# usbjtag.net
KiCad netlist of a schematic drawn in EAGLE
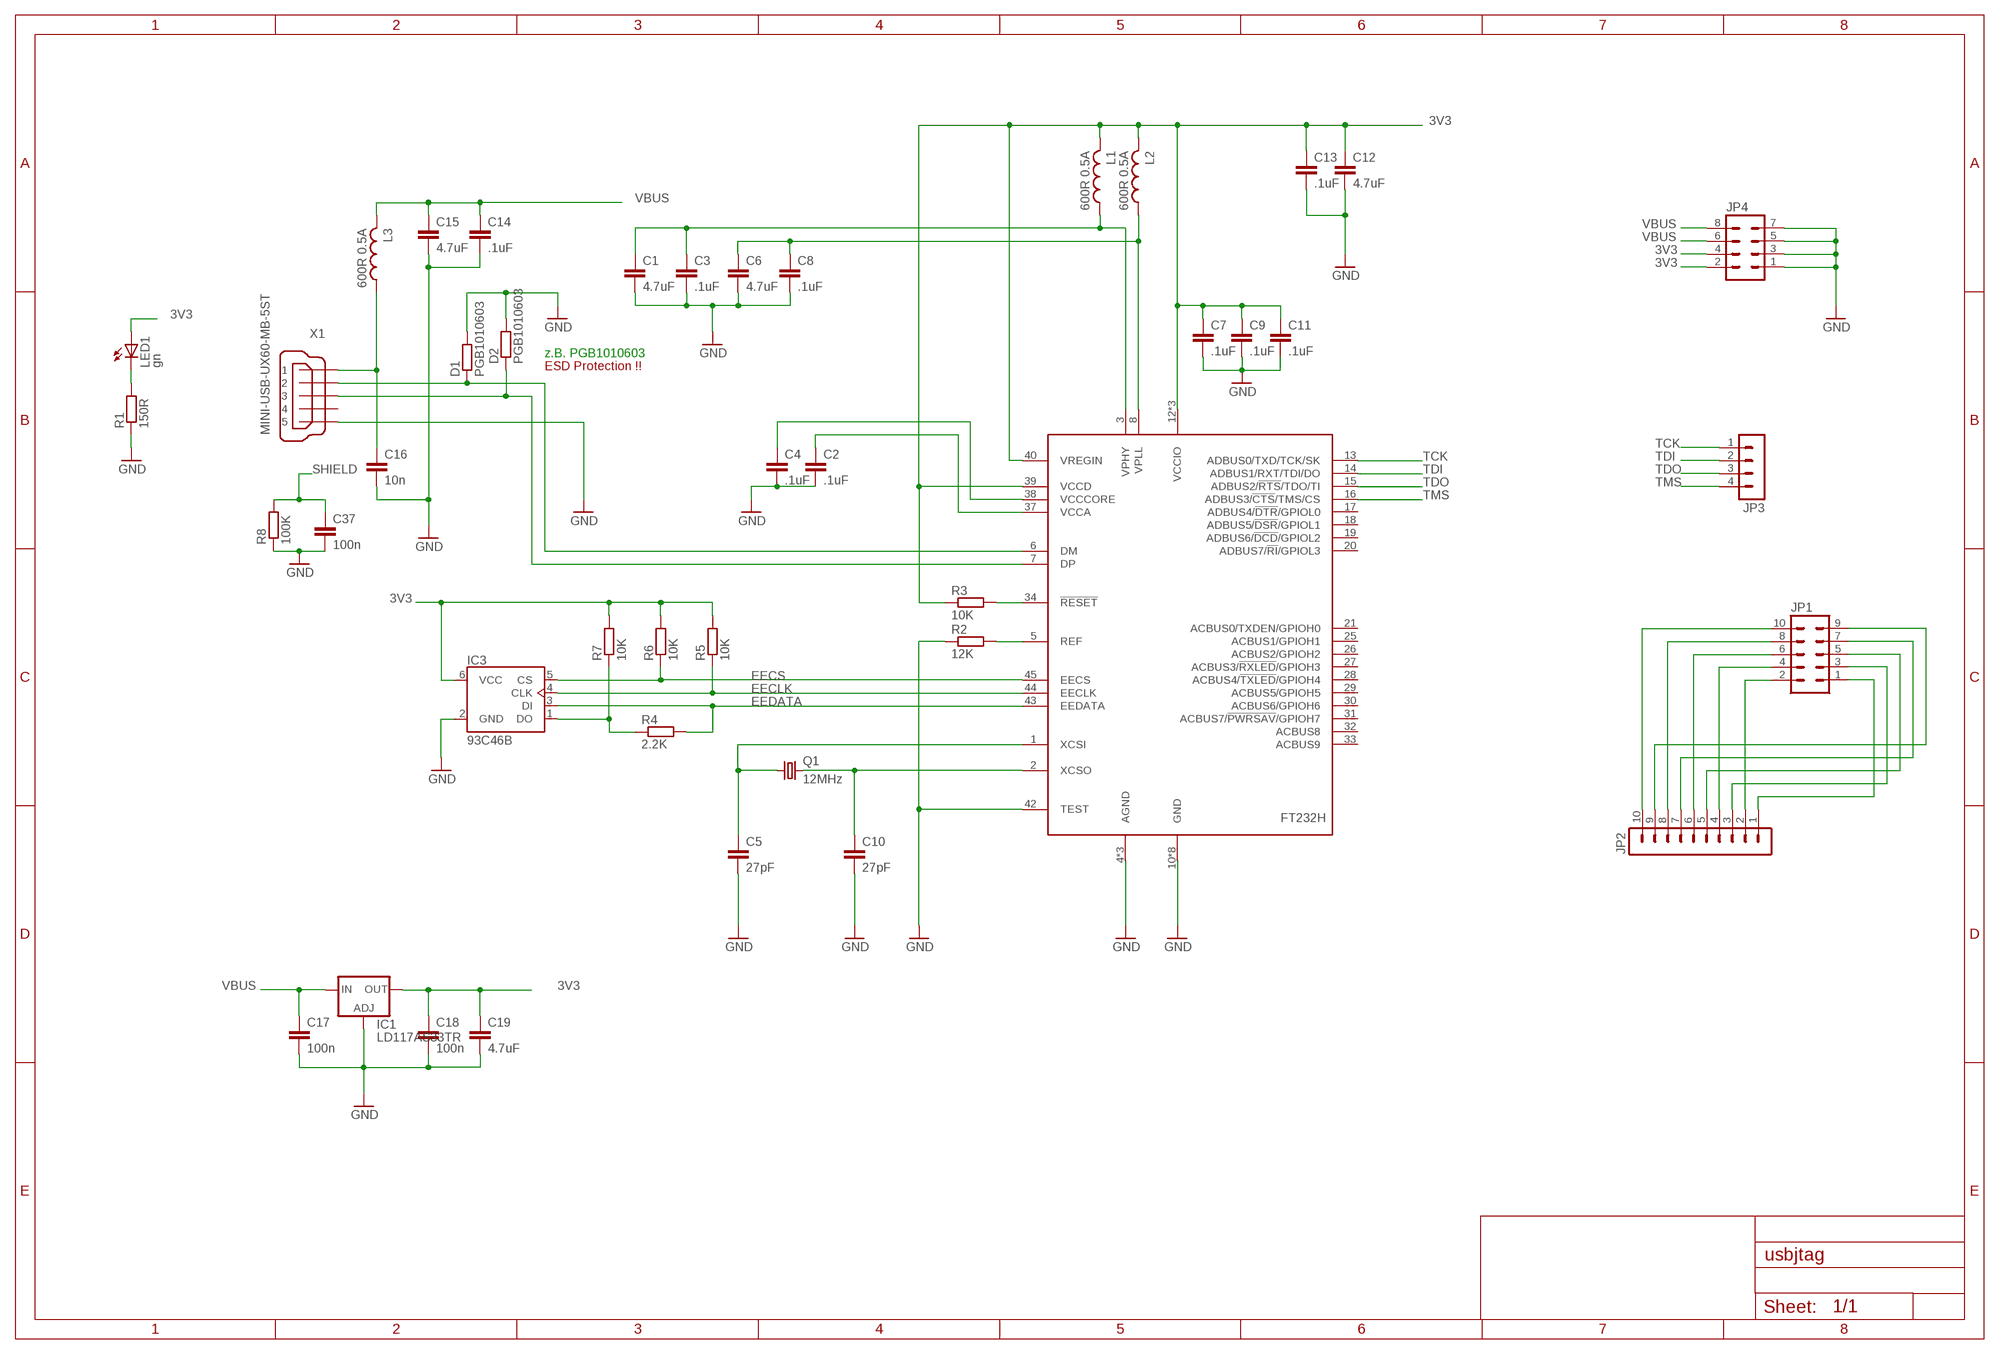
[diagram p0: schematic, sheet 1]

(export (version "E")
  (design (tool "Eeschema 10.0.6"))
  (components
    (comp (ref "C1")
      (value "4.7uF")
      (footprint "eagle-import:C0805")
      (libsource (lib "eagle-import") (part "C-EUC0805"))
    )
    (comp (ref "C2")
      (value ".1uF")
      (footprint "eagle-import:C0805")
      (libsource (lib "eagle-import") (part "C-EUC0805"))
    )
    (comp (ref "C3")
      (value ".1uF")
      (footprint "eagle-import:C0805")
      (libsource (lib "eagle-import") (part "C-EUC0805"))
    )
    (comp (ref "C4")
      (value ".1uF")
      (footprint "eagle-import:C0805")
      (libsource (lib "eagle-import") (part "C-EUC0805"))
    )
    (comp (ref "C5")
      (value "27pF")
      (footprint "eagle-import:C0805")
      (libsource (lib "eagle-import") (part "C-EUC0805"))
    )
    (comp (ref "C6")
      (value "4.7uF")
      (footprint "eagle-import:C0805")
      (libsource (lib "eagle-import") (part "C-EUC0805"))
    )
    (comp (ref "C7")
      (value ".1uF")
      (footprint "eagle-import:C0805")
      (libsource (lib "eagle-import") (part "C-EUC0805"))
    )
    (comp (ref "C8")
      (value ".1uF")
      (footprint "eagle-import:C0805")
      (libsource (lib "eagle-import") (part "C-EUC0805"))
    )
    (comp (ref "C9")
      (value ".1uF")
      (footprint "eagle-import:C0805")
      (libsource (lib "eagle-import") (part "C-EUC0805"))
    )
    (comp (ref "C10")
      (value "27pF")
      (footprint "eagle-import:C0805")
      (libsource (lib "eagle-import") (part "C-EUC0805"))
    )
    (comp (ref "C11")
      (value ".1uF")
      (footprint "eagle-import:C0805")
      (libsource (lib "eagle-import") (part "C-EUC0805"))
    )
    (comp (ref "C12")
      (value "4.7uF")
      (footprint "eagle-import:C0805")
      (libsource (lib "eagle-import") (part "C-EUC0805"))
    )
    (comp (ref "C13")
      (value ".1uF")
      (footprint "eagle-import:C0805")
      (libsource (lib "eagle-import") (part "C-EUC0805"))
    )
    (comp (ref "C14")
      (value ".1uF")
      (footprint "eagle-import:C0805")
      (libsource (lib "eagle-import") (part "C-EUC0805"))
    )
    (comp (ref "C15")
      (value "4.7uF")
      (footprint "eagle-import:C0805")
      (libsource (lib "eagle-import") (part "C-EUC0805"))
    )
    (comp (ref "C16")
      (value "10n")
      (footprint "eagle-import:C0805")
      (libsource (lib "eagle-import") (part "C-EUC0805"))
    )
    (comp (ref "C17")
      (value "100n")
      (footprint "eagle-import:C0805")
      (libsource (lib "eagle-import") (part "C-EUC0805"))
    )
    (comp (ref "C18")
      (value "100n")
      (footprint "eagle-import:C0805")
      (libsource (lib "eagle-import") (part "C-EUC0805"))
    )
    (comp (ref "C19")
      (value "4.7uF")
      (footprint "eagle-import:C0805")
      (libsource (lib "eagle-import") (part "C-EUC0805"))
    )
    (comp (ref "C37")
      (value "100n")
      (footprint "eagle-import:C0805")
      (libsource (lib "eagle-import") (part "C-EUC0805"))
    )
    (comp (ref "D1")
      (value "PGB1010603")
      (footprint "eagle-import:R0603")
      (libsource (lib "eagle-import") (part "R-EU_R0603"))
    )
    (comp (ref "D2")
      (value "PGB1010603")
      (footprint "eagle-import:R0603")
      (libsource (lib "eagle-import") (part "R-EU_R0603"))
    )
    (comp (ref "IC1")
      (value "LD117AS33TR")
      (footprint "eagle-import:SOT223")
      (libsource (lib "eagle-import") (part "LD117A?S33TR"))
    )
    (comp (ref "IC2")
      (value "FT232H")
      (footprint "eagle-import:LQFP48")
      (libsource (lib "eagle-import") (part "FT232H"))
    )
    (comp (ref "IC3")
      (value "93C46B")
      (footprint "eagle-import:SOT23-6")
      (libsource (lib "eagle-import") (part "DIGITAL-EEPROM-MICROWIRE-6P_SOT23"))
    )
    (comp (ref "JP1")
      (value "MA05-2")
      (footprint "eagle-import:MA05-2")
      (libsource (lib "eagle-import") (part "MA05-2"))
    )
    (comp (ref "JP2")
      (value "MA10-1")
      (footprint "eagle-import:MA10-1")
      (libsource (lib "eagle-import") (part "MA10-1"))
    )
    (comp (ref "JP3")
      (value "MA04-1")
      (footprint "eagle-import:MA04-1")
      (libsource (lib "eagle-import") (part "MA04-1"))
    )
    (comp (ref "JP4")
      (value "MA04-2")
      (footprint "eagle-import:MA04-2")
      (libsource (lib "eagle-import") (part "MA04-2"))
    )
    (comp (ref "L1")
      (value "600R 0.5A")
      (footprint "eagle-import:L4532M")
      (libsource (lib "eagle-import") (part "L-USL4532C"))
    )
    (comp (ref "L2")
      (value "600R 0.5A")
      (footprint "eagle-import:L4532M")
      (libsource (lib "eagle-import") (part "L-USL4532C"))
    )
    (comp (ref "L3")
      (value "600R 0.5A")
      (footprint "eagle-import:L4532M")
      (libsource (lib "eagle-import") (part "L-USL4532C"))
    )
    (comp (ref "LED1")
      (value "gn")
      (footprint "eagle-import:CHIPLED_0805")
      (libsource (lib "eagle-import") (part "LEDCHIPLED_0805"))
    )
    (comp (ref "Q1")
      (value "12MHz")
      (footprint "eagle-import:CRYSTAL3.2X2.5MM")
      (libsource (lib "eagle-import") (part "CRYSTAL3.2X2.5"))
    )
    (comp (ref "R1")
      (value "150R")
      (footprint "eagle-import:R0805")
      (libsource (lib "eagle-import") (part "R-EU_R0805"))
    )
    (comp (ref "R2")
      (value "12K")
      (footprint "eagle-import:R0805")
      (libsource (lib "eagle-import") (part "R-EU_R0805"))
    )
    (comp (ref "R3")
      (value "10K")
      (footprint "eagle-import:R0805")
      (libsource (lib "eagle-import") (part "R-EU_R0805"))
    )
    (comp (ref "R4")
      (value "2.2K")
      (footprint "eagle-import:R0805")
      (libsource (lib "eagle-import") (part "R-EU_R0805"))
    )
    (comp (ref "R5")
      (value "10K")
      (footprint "eagle-import:R0805")
      (libsource (lib "eagle-import") (part "R-EU_R0805"))
    )
    (comp (ref "R6")
      (value "10K")
      (footprint "eagle-import:R0805")
      (libsource (lib "eagle-import") (part "R-EU_R0805"))
    )
    (comp (ref "R7")
      (value "10K")
      (footprint "eagle-import:R0805")
      (libsource (lib "eagle-import") (part "R-EU_R0805"))
    )
    (comp (ref "R8")
      (value "100K")
      (footprint "eagle-import:R0805")
      (libsource (lib "eagle-import") (part "R-EU_R0805"))
    )
    (comp (ref "X1")
      (value "MINI-USB-UX60-MB-5ST")
      (footprint "eagle-import:UX60-MB-5ST")
      (libsource (lib "eagle-import") (part "MINI-USB-UX60-MB-5ST"))
    )
  )
  (nets
    (net (code "1") (name "/3V3") (class "Default")
      (node (ref "C11") (pin "1") (pinfunction "1_1") (pintype "passive"))
      (node (ref "C12") (pin "1") (pinfunction "1_1") (pintype "passive"))
      (node (ref "C13") (pin "1") (pinfunction "1_1") (pintype "passive"))
      (node (ref "C18") (pin "1") (pinfunction "1_1") (pintype "passive"))
      (node (ref "C19") (pin "1") (pinfunction "1_1") (pintype "passive"))
      (node (ref "C7") (pin "1") (pinfunction "1_1") (pintype "passive"))
      (node (ref "C9") (pin "1") (pinfunction "1_1") (pintype "passive"))
      (node (ref "IC1") (pin "4") (pinfunction "OUT_4") (pintype "passive"))
      (node (ref "IC2") (pin "12") (pinfunction "VCCIO_12") (pintype "power_in"))
      (node (ref "IC2") (pin "24") (pinfunction "VCCIO_24") (pintype "power_in"))
      (node (ref "IC2") (pin "39") (pinfunction "VCCD_39") (pintype "power_in"))
      (node (ref "IC2") (pin "40") (pinfunction "VREGIN_40") (pintype "power_in"))
      (node (ref "IC2") (pin "46") (pinfunction "VCCIO_46") (pintype "power_in"))
      (node (ref "IC3") (pin "6") (pinfunction "VCC_6") (pintype "input"))
      (node (ref "JP4") (pin "2") (pinfunction "2_2") (pintype "passive"))
      (node (ref "JP4") (pin "4") (pinfunction "4_4") (pintype "passive"))
      (node (ref "L1") (pin "2") (pinfunction "2_2") (pintype "passive"))
      (node (ref "L2") (pin "2") (pinfunction "2_2") (pintype "passive"))
      (node (ref "LED1") (pin "A") (pinfunction "A_A") (pintype "passive"))
      (node (ref "R3") (pin "1") (pinfunction "1_1") (pintype "passive"))
      (node (ref "R5") (pin "2") (pinfunction "2_2") (pintype "passive"))
      (node (ref "R6") (pin "2") (pinfunction "2_2") (pintype "passive"))
      (node (ref "R7") (pin "2") (pinfunction "2_2") (pintype "passive"))
    )
    (net (code "2") (name "/EECLK") (class "Default")
      (node (ref "IC2") (pin "44") (pinfunction "EECLK_44") (pintype "bidirectional"))
      (node (ref "IC3") (pin "4") (pinfunction "CLK_4") (pintype "input"))
      (node (ref "R5") (pin "1") (pinfunction "1_1") (pintype "passive"))
    )
    (net (code "3") (name "/EECS") (class "Default")
      (node (ref "IC2") (pin "45") (pinfunction "EECS_45") (pintype "bidirectional"))
      (node (ref "IC3") (pin "5") (pinfunction "CS_5") (pintype "input"))
      (node (ref "R6") (pin "1") (pinfunction "1_1") (pintype "passive"))
    )
    (net (code "4") (name "/EEDATA") (class "Default")
      (node (ref "IC2") (pin "43") (pinfunction "EEDATA_43") (pintype "bidirectional"))
      (node (ref "IC3") (pin "3") (pinfunction "DI_3") (pintype "input"))
      (node (ref "R4") (pin "2") (pinfunction "2_2") (pintype "passive"))
    )
    (net (code "5") (name "/SHIELD") (class "Default")
      (node (ref "C37") (pin "1") (pinfunction "1_1") (pintype "passive"))
      (node (ref "R8") (pin "2") (pinfunction "2_2") (pintype "passive"))
    )
    (net (code "6") (name "/TCK") (class "Default")
      (node (ref "IC2") (pin "13") (pinfunction "ADBUS0/TXD/TCK/SK_13") (pintype "bidirectional"))
      (node (ref "JP3") (pin "1") (pinfunction "1_1") (pintype "passive"))
    )
    (net (code "7") (name "/TDI") (class "Default")
      (node (ref "IC2") (pin "14") (pinfunction "ADBUS1/RXT/TDI/DO_14") (pintype "bidirectional"))
      (node (ref "JP3") (pin "2") (pinfunction "2_2") (pintype "passive"))
    )
    (net (code "8") (name "/TDO") (class "Default")
      (node (ref "IC2") (pin "15") (pinfunction "ADBUS2/~{RTS}/TDO/TI_15") (pintype "bidirectional"))
      (node (ref "JP3") (pin "3") (pinfunction "3_3") (pintype "passive"))
    )
    (net (code "9") (name "/TMS") (class "Default")
      (node (ref "IC2") (pin "16") (pinfunction "ADBUS3/~{CTS}/TMS/CS_16") (pintype "bidirectional"))
      (node (ref "JP3") (pin "4") (pinfunction "4_4") (pintype "passive"))
    )
    (net (code "10") (name "/VBUS") (class "Default")
      (node (ref "C14") (pin "1") (pinfunction "1_1") (pintype "passive"))
      (node (ref "C15") (pin "1") (pinfunction "1_1") (pintype "passive"))
      (node (ref "C17") (pin "1") (pinfunction "1_1") (pintype "passive"))
      (node (ref "IC1") (pin "3") (pinfunction "IN_3") (pintype "input"))
      (node (ref "JP4") (pin "6") (pinfunction "6_6") (pintype "passive"))
      (node (ref "JP4") (pin "8") (pinfunction "8_8") (pintype "passive"))
      (node (ref "L3") (pin "2") (pinfunction "2_2") (pintype "passive"))
    )
    (net (code "11") (name "GND") (class "Default")
      (node (ref "C1") (pin "2") (pinfunction "2_2") (pintype "passive"))
      (node (ref "C10") (pin "2") (pinfunction "2_2") (pintype "passive"))
      (node (ref "C11") (pin "2") (pinfunction "2_2") (pintype "passive"))
      (node (ref "C12") (pin "2") (pinfunction "2_2") (pintype "passive"))
      (node (ref "C13") (pin "2") (pinfunction "2_2") (pintype "passive"))
      (node (ref "C14") (pin "2") (pinfunction "2_2") (pintype "passive"))
      (node (ref "C15") (pin "2") (pinfunction "2_2") (pintype "passive"))
      (node (ref "C16") (pin "2") (pinfunction "2_2") (pintype "passive"))
      (node (ref "C17") (pin "2") (pinfunction "2_2") (pintype "passive"))
      (node (ref "C18") (pin "2") (pinfunction "2_2") (pintype "passive"))
      (node (ref "C19") (pin "2") (pinfunction "2_2") (pintype "passive"))
      (node (ref "C2") (pin "2") (pinfunction "2_2") (pintype "passive"))
      (node (ref "C3") (pin "2") (pinfunction "2_2") (pintype "passive"))
      (node (ref "C37") (pin "2") (pinfunction "2_2") (pintype "passive"))
      (node (ref "C4") (pin "2") (pinfunction "2_2") (pintype "passive"))
      (node (ref "C5") (pin "2") (pinfunction "2_2") (pintype "passive"))
      (node (ref "C6") (pin "2") (pinfunction "2_2") (pintype "passive"))
      (node (ref "C7") (pin "2") (pinfunction "2_2") (pintype "passive"))
      (node (ref "C8") (pin "2") (pinfunction "2_2") (pintype "passive"))
      (node (ref "C9") (pin "2") (pinfunction "2_2") (pintype "passive"))
      (node (ref "D1") (pin "2") (pinfunction "2_2") (pintype "passive"))
      (node (ref "D2") (pin "2") (pinfunction "2_2") (pintype "passive"))
      (node (ref "IC1") (pin "1") (pinfunction "ADJ_1") (pintype "input"))
      (node (ref "IC2") (pin "10") (pinfunction "GND_10") (pintype "power_in"))
      (node (ref "IC2") (pin "11") (pinfunction "GND_11") (pintype "power_in"))
      (node (ref "IC2") (pin "22") (pinfunction "GND_22") (pintype "power_in"))
      (node (ref "IC2") (pin "23") (pinfunction "GND_23") (pintype "power_in"))
      (node (ref "IC2") (pin "35") (pinfunction "GND_35") (pintype "power_in"))
      (node (ref "IC2") (pin "36") (pinfunction "GND_36") (pintype "power_in"))
      (node (ref "IC2") (pin "4") (pinfunction "AGND_4") (pintype "power_in"))
      (node (ref "IC2") (pin "41") (pinfunction "AGND_41") (pintype "power_in"))
      (node (ref "IC2") (pin "42") (pinfunction "TEST_42") (pintype "bidirectional"))
      (node (ref "IC2") (pin "47") (pinfunction "GND_47") (pintype "power_in"))
      (node (ref "IC2") (pin "48") (pinfunction "GND_48") (pintype "power_in"))
      (node (ref "IC2") (pin "9") (pinfunction "AGND_9") (pintype "power_in"))
      (node (ref "IC3") (pin "2") (pinfunction "GND_2") (pintype "power_in"))
      (node (ref "JP4") (pin "1") (pinfunction "1_1") (pintype "passive"))
      (node (ref "JP4") (pin "3") (pinfunction "3_3") (pintype "passive"))
      (node (ref "JP4") (pin "5") (pinfunction "5_5") (pintype "passive"))
      (node (ref "JP4") (pin "7") (pinfunction "7_7") (pintype "passive"))
      (node (ref "R1") (pin "1") (pinfunction "1_1") (pintype "passive"))
      (node (ref "R2") (pin "1") (pinfunction "1_1") (pintype "passive"))
      (node (ref "R8") (pin "1") (pinfunction "1_1") (pintype "passive"))
      (node (ref "X1") (pin "5") (pinfunction "5_5") (pintype "input"))
    )
    (net (code "12") (name "Net-(C16-Pad1)") (class "Default")
      (node (ref "C16") (pin "1") (pinfunction "1_1") (pintype "passive"))
      (node (ref "L3") (pin "1") (pinfunction "1_1") (pintype "passive"))
      (node (ref "X1") (pin "1") (pinfunction "1_1") (pintype "input"))
    )
    (net (code "13") (name "Net-(IC2-DM)") (class "Default")
      (node (ref "D1") (pin "1") (pinfunction "1_1") (pintype "passive"))
      (node (ref "IC2") (pin "6") (pinfunction "DM_6") (pintype "bidirectional"))
      (node (ref "X1") (pin "2") (pinfunction "2_2") (pintype "input"))
    )
    (net (code "14") (name "Net-(IC2-DP)") (class "Default")
      (node (ref "D2") (pin "1") (pinfunction "1_1") (pintype "passive"))
      (node (ref "IC2") (pin "7") (pinfunction "DP_7") (pintype "bidirectional"))
      (node (ref "X1") (pin "3") (pinfunction "3_3") (pintype "input"))
    )
    (net (code "15") (name "Net-(IC2-REF)") (class "Default")
      (node (ref "IC2") (pin "5") (pinfunction "REF_5") (pintype "bidirectional"))
      (node (ref "R2") (pin "2") (pinfunction "2_2") (pintype "passive"))
    )
    (net (code "16") (name "Net-(IC2-VCCA)") (class "Default")
      (node (ref "C2") (pin "1") (pinfunction "1_1") (pintype "passive"))
      (node (ref "IC2") (pin "37") (pinfunction "VCCA_37") (pintype "power_in"))
    )
    (net (code "17") (name "Net-(IC2-VCCCORE)") (class "Default")
      (node (ref "C4") (pin "1") (pinfunction "1_1") (pintype "passive"))
      (node (ref "IC2") (pin "38") (pinfunction "VCCCORE_38") (pintype "power_in"))
    )
    (net (code "18") (name "Net-(IC2-VPHY)") (class "Default")
      (node (ref "C1") (pin "1") (pinfunction "1_1") (pintype "passive"))
      (node (ref "C3") (pin "1") (pinfunction "1_1") (pintype "passive"))
      (node (ref "IC2") (pin "3") (pinfunction "VPHY_3") (pintype "power_in"))
      (node (ref "L1") (pin "1") (pinfunction "1_1") (pintype "passive"))
    )
    (net (code "19") (name "Net-(IC2-VPLL)") (class "Default")
      (node (ref "C6") (pin "1") (pinfunction "1_1") (pintype "passive"))
      (node (ref "C8") (pin "1") (pinfunction "1_1") (pintype "passive"))
      (node (ref "IC2") (pin "8") (pinfunction "VPLL_8") (pintype "power_in"))
      (node (ref "L2") (pin "1") (pinfunction "1_1") (pintype "passive"))
    )
    (net (code "20") (name "Net-(IC2-XCSI)") (class "Default")
      (node (ref "C5") (pin "1") (pinfunction "1_1") (pintype "passive"))
      (node (ref "IC2") (pin "1") (pinfunction "XCSI_1") (pintype "bidirectional"))
      (node (ref "Q1") (pin "1") (pinfunction "1_1") (pintype "passive"))
    )
    (net (code "21") (name "Net-(IC2-XCSO)") (class "Default")
      (node (ref "C10") (pin "1") (pinfunction "1_1") (pintype "passive"))
      (node (ref "IC2") (pin "2") (pinfunction "XCSO_2") (pintype "bidirectional"))
      (node (ref "Q1") (pin "3") (pinfunction "2_3") (pintype "passive"))
    )
    (net (code "22") (name "Net-(IC2-~{RESET})") (class "Default")
      (node (ref "IC2") (pin "34") (pinfunction "~{RESET}_34") (pintype "input"))
      (node (ref "R3") (pin "2") (pinfunction "2_2") (pintype "passive"))
    )
    (net (code "23") (name "Net-(IC3-DO)") (class "Default")
      (node (ref "IC3") (pin "1") (pinfunction "DO_1") (pintype "output"))
      (node (ref "R4") (pin "1") (pinfunction "1_1") (pintype "passive"))
      (node (ref "R7") (pin "1") (pinfunction "1_1") (pintype "passive"))
    )
    (net (code "24") (name "Net-(JP1-Pad1)") (class "Default")
      (node (ref "JP1") (pin "1") (pinfunction "1_1") (pintype "passive"))
      (node (ref "JP2") (pin "1") (pinfunction "1_1") (pintype "passive"))
    )
    (net (code "25") (name "Net-(JP1-Pad2)") (class "Default")
      (node (ref "JP1") (pin "2") (pinfunction "2_2") (pintype "passive"))
      (node (ref "JP2") (pin "2") (pinfunction "2_2") (pintype "passive"))
    )
    (net (code "26") (name "Net-(JP1-Pad3)") (class "Default")
      (node (ref "JP1") (pin "3") (pinfunction "3_3") (pintype "passive"))
      (node (ref "JP2") (pin "3") (pinfunction "3_3") (pintype "passive"))
    )
    (net (code "27") (name "Net-(JP1-Pad4)") (class "Default")
      (node (ref "JP1") (pin "4") (pinfunction "4_4") (pintype "passive"))
      (node (ref "JP2") (pin "4") (pinfunction "4_4") (pintype "passive"))
    )
    (net (code "28") (name "Net-(JP1-Pad5)") (class "Default")
      (node (ref "JP1") (pin "5") (pinfunction "5_5") (pintype "passive"))
      (node (ref "JP2") (pin "5") (pinfunction "5_5") (pintype "passive"))
    )
    (net (code "29") (name "Net-(JP1-Pad6)") (class "Default")
      (node (ref "JP1") (pin "6") (pinfunction "6_6") (pintype "passive"))
      (node (ref "JP2") (pin "6") (pinfunction "6_6") (pintype "passive"))
    )
    (net (code "30") (name "Net-(JP1-Pad7)") (class "Default")
      (node (ref "JP1") (pin "7") (pinfunction "7_7") (pintype "passive"))
      (node (ref "JP2") (pin "7") (pinfunction "7_7") (pintype "passive"))
    )
    (net (code "31") (name "Net-(JP1-Pad8)") (class "Default")
      (node (ref "JP1") (pin "8") (pinfunction "8_8") (pintype "passive"))
      (node (ref "JP2") (pin "8") (pinfunction "8_8") (pintype "passive"))
    )
    (net (code "32") (name "Net-(JP1-Pad9)") (class "Default")
      (node (ref "JP1") (pin "9") (pinfunction "9_9") (pintype "passive"))
      (node (ref "JP2") (pin "9") (pinfunction "9_9") (pintype "passive"))
    )
    (net (code "33") (name "Net-(JP1-Pad10)") (class "Default")
      (node (ref "JP1") (pin "10") (pinfunction "10_10") (pintype "passive"))
      (node (ref "JP2") (pin "10") (pinfunction "10_10") (pintype "passive"))
    )
    (net (code "34") (name "Net-(LED1-PadC)") (class "Default")
      (node (ref "LED1") (pin "C") (pinfunction "C_C") (pintype "passive"))
      (node (ref "R1") (pin "2") (pinfunction "2_2") (pintype "passive"))
    )
    (net (code "35") (name "unconnected-(IC2-ACBUS0{slash}TXDEN{slash}GPIOH0-Pad21)") (class "Default")
      (node (ref "IC2") (pin "21") (pinfunction "ACBUS0/TXDEN/GPIOH0_21") (pintype "bidirectional"))
    )
    (net (code "36") (name "unconnected-(IC2-ACBUS1{slash}GPIOH1-Pad25)") (class "Default")
      (node (ref "IC2") (pin "25") (pinfunction "ACBUS1/GPIOH1_25") (pintype "bidirectional"))
    )
    (net (code "37") (name "unconnected-(IC2-ACBUS2{slash}GPIOH2-Pad26)") (class "Default")
      (node (ref "IC2") (pin "26") (pinfunction "ACBUS2/GPIOH2_26") (pintype "bidirectional"))
    )
    (net (code "38") (name "unconnected-(IC2-ACBUS3{slash}~{RXLED}{slash}GPIOH3-Pad27)") (class "Default")
      (node (ref "IC2") (pin "27") (pinfunction "ACBUS3/~{RXLED}/GPIOH3_27") (pintype "bidirectional"))
    )
    (net (code "39") (name "unconnected-(IC2-ACBUS4{slash}~{TXLED}{slash}GPIOH4-Pad28)") (class "Default")
      (node (ref "IC2") (pin "28") (pinfunction "ACBUS4/~{TXLED}/GPIOH4_28") (pintype "bidirectional"))
    )
    (net (code "40") (name "unconnected-(IC2-ACBUS5{slash}GPIOH5-Pad29)") (class "Default")
      (node (ref "IC2") (pin "29") (pinfunction "ACBUS5/GPIOH5_29") (pintype "bidirectional"))
    )
    (net (code "41") (name "unconnected-(IC2-ACBUS6{slash}GPIOH6-Pad30)") (class "Default")
      (node (ref "IC2") (pin "30") (pinfunction "ACBUS6/GPIOH6_30") (pintype "bidirectional"))
    )
    (net (code "42") (name "unconnected-(IC2-ACBUS7{slash}~{PWRSAV}{slash}GPIOH7-Pad31)") (class "Default")
      (node (ref "IC2") (pin "31") (pinfunction "ACBUS7/~{PWRSAV}/GPIOH7_31") (pintype "bidirectional"))
    )
    (net (code "43") (name "unconnected-(IC2-ACBUS8-Pad32)") (class "Default")
      (node (ref "IC2") (pin "32") (pinfunction "ACBUS8_32") (pintype "bidirectional"))
    )
    (net (code "44") (name "unconnected-(IC2-ACBUS9-Pad33)") (class "Default")
      (node (ref "IC2") (pin "33") (pinfunction "ACBUS9_33") (pintype "bidirectional"))
    )
    (net (code "45") (name "unconnected-(IC2-ADBUS4{slash}~{DTR}{slash}GPIOL0-Pad17)") (class "Default")
      (node (ref "IC2") (pin "17") (pinfunction "ADBUS4/~{DTR}/GPIOL0_17") (pintype "bidirectional"))
    )
    (net (code "46") (name "unconnected-(IC2-ADBUS5{slash}~{DSR}{slash}GPIOL1-Pad18)") (class "Default")
      (node (ref "IC2") (pin "18") (pinfunction "ADBUS5/~{DSR}/GPIOL1_18") (pintype "bidirectional"))
    )
    (net (code "47") (name "unconnected-(IC2-ADBUS6{slash}~{DCD}{slash}GPIOL2-Pad19)") (class "Default")
      (node (ref "IC2") (pin "19") (pinfunction "ADBUS6/~{DCD}/GPIOL2_19") (pintype "bidirectional"))
    )
    (net (code "48") (name "unconnected-(IC2-ADBUS7{slash}~{RI}{slash}GPIOL3-Pad20)") (class "Default")
      (node (ref "IC2") (pin "20") (pinfunction "ADBUS7/~{RI}/GPIOL3_20") (pintype "bidirectional"))
    )
    (net (code "49") (name "unconnected-(X1-Pad4)") (class "Default")
      (node (ref "X1") (pin "4") (pinfunction "4_4") (pintype "input"))
    )
  )
)
